# RGB_Panel_Shield_for_Arduino.net
KiCad netlist of a schematic drawn in EAGLE
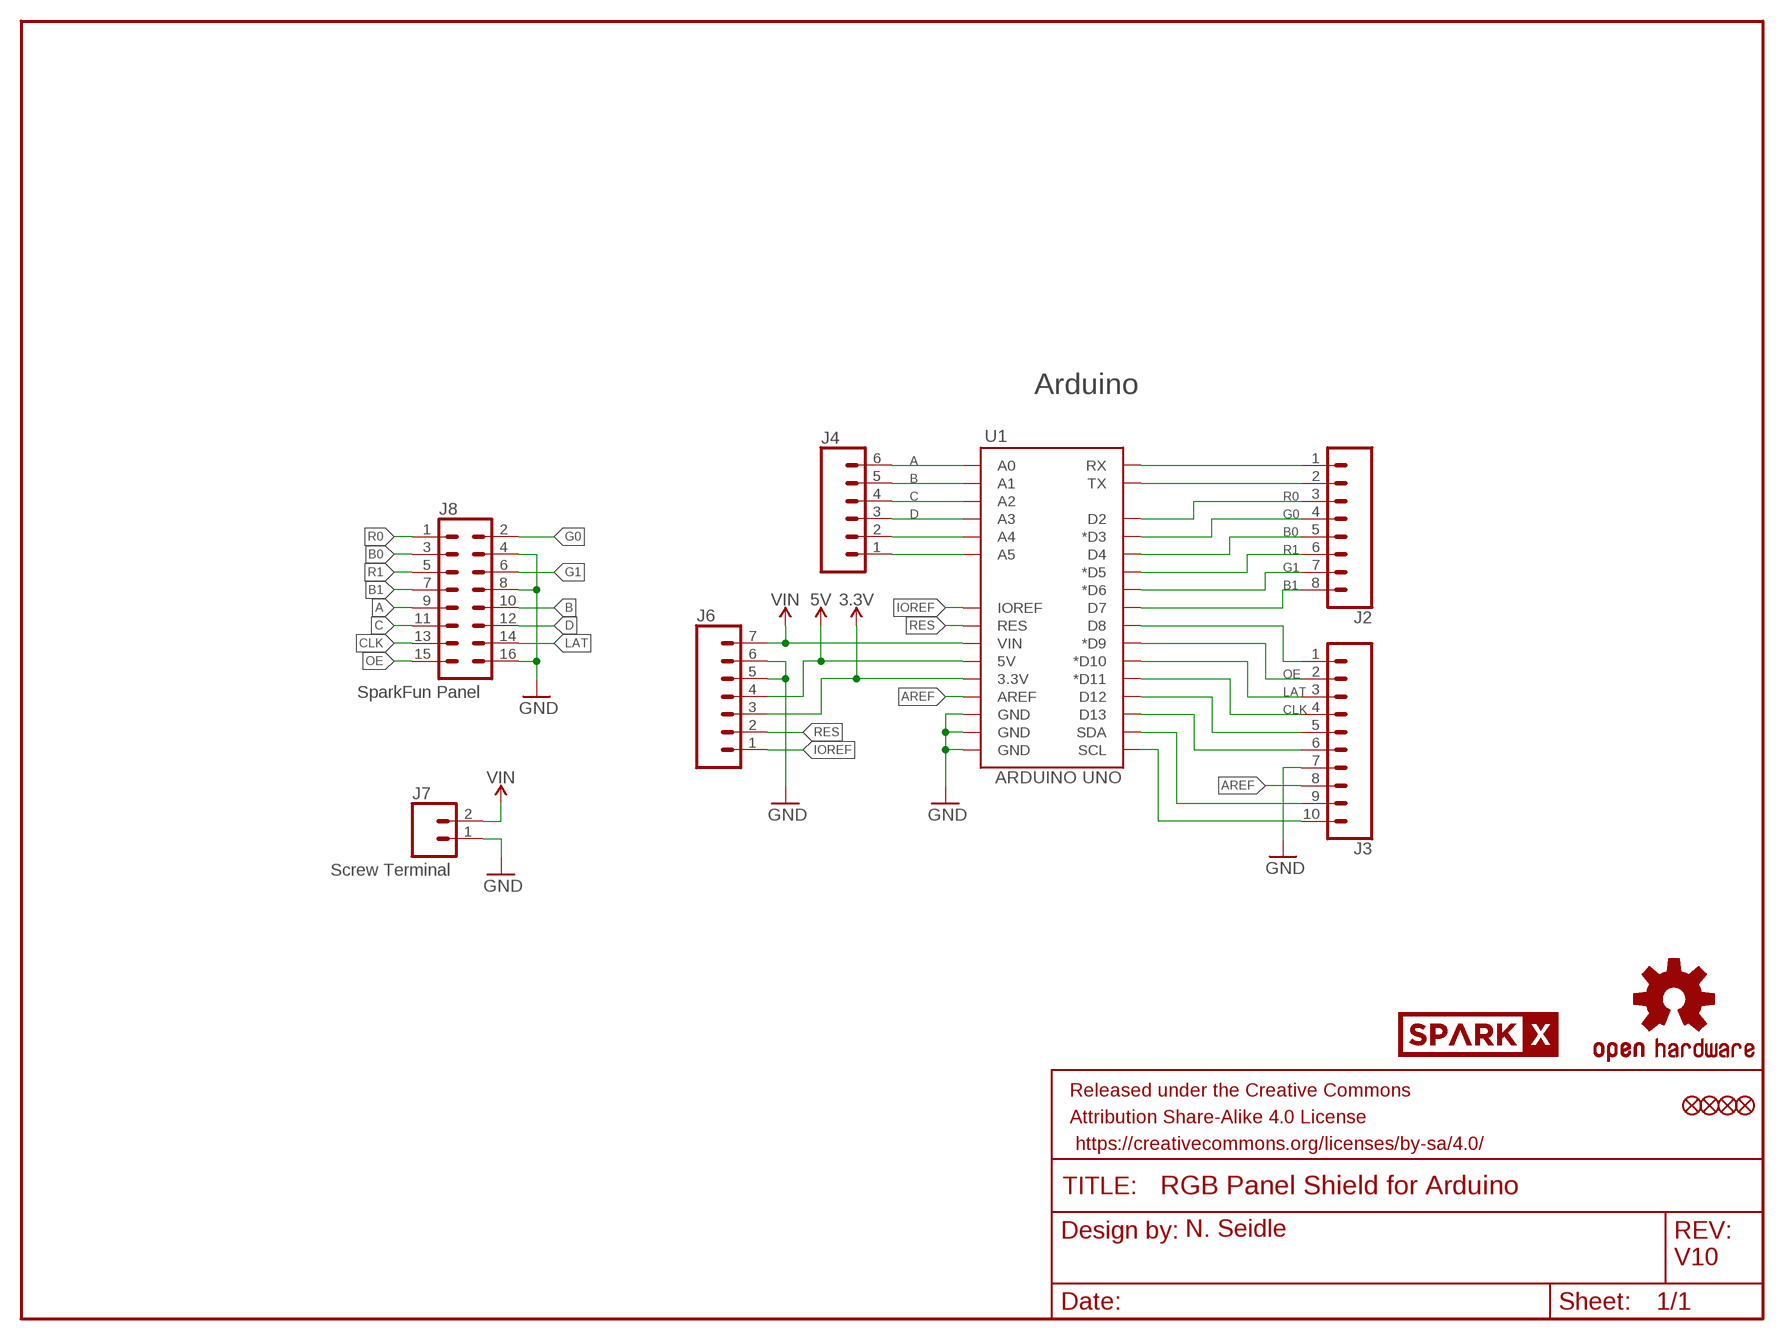
[diagram p0: schematic, sheet 1]

(export (version "E")
  (design (tool "Eeschema 10.0.6"))
  (components
    (comp (ref "FD1")
      (value "FIDUCIAL1X2")
      (footprint "eagle-import:FIDUCIAL-1X2")
      (libsource (lib "eagle-import") (part "FIDUCIAL1X2"))
    )
    (comp (ref "FD2")
      (value "FIDUCIAL1X2")
      (footprint "eagle-import:FIDUCIAL-1X2")
      (libsource (lib "eagle-import") (part "FIDUCIAL1X2"))
    )
    (comp (ref "FD3")
      (value "FIDUCIAL1X2")
      (footprint "eagle-import:FIDUCIAL-1X2")
      (libsource (lib "eagle-import") (part "FIDUCIAL1X2"))
    )
    (comp (ref "FD4")
      (value "FIDUCIAL1X2")
      (footprint "eagle-import:FIDUCIAL-1X2")
      (libsource (lib "eagle-import") (part "FIDUCIAL1X2"))
    )
    (comp (ref "FRAME1")
      (value "FRAME-LETTER")
      (footprint "eagle-import:CREATIVE_COMMONS")
      (libsource (lib "eagle-import") (part "FRAME-LETTER"))
    )
    (comp (ref "J2")
      (value "CONN_08NO_SILK_FEMALE_PTH")
      (footprint "eagle-import:1X08_NO_SILK")
      (libsource (lib "eagle-import") (part "CONN_08NO_SILK_FEMALE_PTH"))
    )
    (comp (ref "J3")
      (value "CONN_10NO_SILK_PTH_FEMALE")
      (footprint "eagle-import:1X10_NO_SILK")
      (libsource (lib "eagle-import") (part "CONN_10NO_SILK_PTH_FEMALE"))
    )
    (comp (ref "J4")
      (value "CONN_06NO_SILK_FEMALE_PTH")
      (footprint "eagle-import:1X06_NO_SILK")
      (libsource (lib "eagle-import") (part "CONN_06NO_SILK_FEMALE_PTH"))
    )
    (comp (ref "J6")
      (value "CONN_07NO_SILK")
      (footprint "eagle-import:1X07_NO_SILK")
      (libsource (lib "eagle-import") (part "CONN_07NO_SILK"))
    )
    (comp (ref "J7")
      (value "Screw Terminal")
      (footprint "eagle-import:SCREWTERMINAL-5MM-2")
      (libsource (lib "eagle-import") (part "CONN_025MM"))
    )
    (comp (ref "J8")
      (value "SparkFun Panel")
      (footprint "eagle-import:2X8-SHROUDED_LOCK")
      (libsource (lib "eagle-import") (part "CONN_08X2_SHROUD"))
    )
    (comp (ref "LOGO1")
      (value "OSHW-LOGOMINI")
      (footprint "eagle-import:OSHW-LOGO-MINI")
      (libsource (lib "eagle-import") (part "OSHW-LOGOMINI"))
    )
    (comp (ref "U$91")
      (value "SPARKX-LOGO4")
      (footprint "eagle-import:SPARKX-MEDIUM")
      (libsource (lib "eagle-import") (part "SPARKX-LOGO4"))
    )
    (comp (ref "U1")
      (value "ARDUINO UNO")
      (footprint "eagle-import:UNO_R3_SHIELD_NOLABELS")
      (libsource (lib "eagle-import") (part "ARDUINO_R3_SHIELDNOLABELS"))
    )
  )
  (nets
    (net (code "1") (name "3.3V") (class "Default")
      (node (ref "J6") (pin "3") (pinfunction "3_3") (pintype "passive"))
      (node (ref "U1") (pin "3.3V") (pinfunction "3.3V_3.3V") (pintype "bidirectional"))
    )
    (net (code "2") (name "5V") (class "Default")
      (node (ref "J6") (pin "4") (pinfunction "4_4") (pintype "passive"))
      (node (ref "U1") (pin "5V") (pinfunction "5V_5V") (pintype "bidirectional"))
    )
    (net (code "3") (name "A") (class "Default")
      (node (ref "J4") (pin "6") (pinfunction "6_6") (pintype "passive"))
      (node (ref "J8") (pin "9") (pinfunction "9_9") (pintype "passive"))
      (node (ref "U1") (pin "A0") (pinfunction "A0_A0") (pintype "bidirectional"))
    )
    (net (code "4") (name "AREF") (class "Default")
      (node (ref "J3") (pin "8") (pinfunction "8_8") (pintype "passive"))
      (node (ref "U1") (pin "AREF") (pinfunction "AREF_AREF") (pintype "bidirectional"))
    )
    (net (code "5") (name "B") (class "Default")
      (node (ref "J4") (pin "5") (pinfunction "5_5") (pintype "passive"))
      (node (ref "J8") (pin "10") (pinfunction "10_10") (pintype "passive"))
      (node (ref "U1") (pin "A1") (pinfunction "A1_A1") (pintype "bidirectional"))
    )
    (net (code "6") (name "B0") (class "Default")
      (node (ref "J2") (pin "5") (pinfunction "5_5") (pintype "passive"))
      (node (ref "J8") (pin "3") (pinfunction "3_3") (pintype "passive"))
      (node (ref "U1") (pin "D4") (pinfunction "D4_D4") (pintype "bidirectional"))
    )
    (net (code "7") (name "B1") (class "Default")
      (node (ref "J2") (pin "8") (pinfunction "8_8") (pintype "passive"))
      (node (ref "J8") (pin "7") (pinfunction "7_7") (pintype "passive"))
      (node (ref "U1") (pin "D7") (pinfunction "D7_D7") (pintype "bidirectional"))
    )
    (net (code "8") (name "C") (class "Default")
      (node (ref "J4") (pin "4") (pinfunction "4_4") (pintype "passive"))
      (node (ref "J8") (pin "11") (pinfunction "11_11") (pintype "passive"))
      (node (ref "U1") (pin "A2") (pinfunction "A2_A2") (pintype "bidirectional"))
    )
    (net (code "9") (name "CLK") (class "Default")
      (node (ref "J3") (pin "4") (pinfunction "4_4") (pintype "passive"))
      (node (ref "J8") (pin "13") (pinfunction "13_13") (pintype "passive"))
      (node (ref "U1") (pin "D11") (pinfunction "*D11_D11") (pintype "bidirectional"))
    )
    (net (code "10") (name "D") (class "Default")
      (node (ref "J4") (pin "3") (pinfunction "3_3") (pintype "passive"))
      (node (ref "J8") (pin "12") (pinfunction "12_12") (pintype "passive"))
      (node (ref "U1") (pin "A3") (pinfunction "A3_A3") (pintype "bidirectional"))
    )
    (net (code "11") (name "G0") (class "Default")
      (node (ref "J2") (pin "4") (pinfunction "4_4") (pintype "passive"))
      (node (ref "J8") (pin "2") (pinfunction "2_2") (pintype "passive"))
      (node (ref "U1") (pin "D3") (pinfunction "*D3_D3") (pintype "bidirectional"))
    )
    (net (code "12") (name "G1") (class "Default")
      (node (ref "J2") (pin "7") (pinfunction "7_7") (pintype "passive"))
      (node (ref "J8") (pin "6") (pinfunction "6_6") (pintype "passive"))
      (node (ref "U1") (pin "D6") (pinfunction "*D6_D6") (pintype "bidirectional"))
    )
    (net (code "13") (name "GND") (class "Default")
      (node (ref "J3") (pin "7") (pinfunction "7_7") (pintype "passive"))
      (node (ref "J6") (pin "5") (pinfunction "5_5") (pintype "passive"))
      (node (ref "J6") (pin "6") (pinfunction "6_6") (pintype "passive"))
      (node (ref "J7") (pin "1") (pinfunction "1_1") (pintype "passive"))
      (node (ref "J8") (pin "16") (pinfunction "16_16") (pintype "passive"))
      (node (ref "J8") (pin "4") (pinfunction "4_4") (pintype "passive"))
      (node (ref "J8") (pin "8") (pinfunction "8_8") (pintype "passive"))
      (node (ref "U1") (pin "GND@0") (pinfunction "GND_GND@0") (pintype "bidirectional"))
      (node (ref "U1") (pin "GND@1") (pinfunction "GND_GND@1") (pintype "bidirectional"))
      (node (ref "U1") (pin "GND@2") (pinfunction "GND_GND@2") (pintype "bidirectional"))
    )
    (net (code "14") (name "IOREF") (class "Default")
      (node (ref "J6") (pin "1") (pinfunction "1_1") (pintype "passive"))
      (node (ref "U1") (pin "IOREF") (pinfunction "IOREF_IOREF") (pintype "bidirectional"))
    )
    (net (code "15") (name "LAT") (class "Default")
      (node (ref "J3") (pin "3") (pinfunction "3_3") (pintype "passive"))
      (node (ref "J8") (pin "14") (pinfunction "14_14") (pintype "passive"))
      (node (ref "U1") (pin "D10") (pinfunction "*D10_D10") (pintype "bidirectional"))
    )
    (net (code "16") (name "Net-(J2-Pad1)") (class "Default")
      (node (ref "J2") (pin "1") (pinfunction "1_1") (pintype "passive"))
      (node (ref "U1") (pin "RX") (pinfunction "RX_RX") (pintype "bidirectional"))
    )
    (net (code "17") (name "Net-(J2-Pad2)") (class "Default")
      (node (ref "J2") (pin "2") (pinfunction "2_2") (pintype "passive"))
      (node (ref "U1") (pin "TX") (pinfunction "TX_TX") (pintype "bidirectional"))
    )
    (net (code "18") (name "Net-(J3-Pad1)") (class "Default")
      (node (ref "J3") (pin "1") (pinfunction "1_1") (pintype "passive"))
      (node (ref "U1") (pin "D8") (pinfunction "D8_D8") (pintype "bidirectional"))
    )
    (net (code "19") (name "Net-(J3-Pad5)") (class "Default")
      (node (ref "J3") (pin "5") (pinfunction "5_5") (pintype "passive"))
      (node (ref "U1") (pin "D12") (pinfunction "D12_D12") (pintype "bidirectional"))
    )
    (net (code "20") (name "Net-(J3-Pad6)") (class "Default")
      (node (ref "J3") (pin "6") (pinfunction "6_6") (pintype "passive"))
      (node (ref "U1") (pin "D13") (pinfunction "D13_D13") (pintype "bidirectional"))
    )
    (net (code "21") (name "Net-(J3-Pad9)") (class "Default")
      (node (ref "J3") (pin "9") (pinfunction "9_9") (pintype "passive"))
      (node (ref "U1") (pin "SDA") (pinfunction "SDA_SDA") (pintype "bidirectional"))
    )
    (net (code "22") (name "Net-(J3-Pad10)") (class "Default")
      (node (ref "J3") (pin "10") (pinfunction "10_10") (pintype "passive"))
      (node (ref "U1") (pin "SCL") (pinfunction "SCL_SCL") (pintype "bidirectional"))
    )
    (net (code "23") (name "Net-(J4-Pad1)") (class "Default")
      (node (ref "J4") (pin "1") (pinfunction "1_1") (pintype "passive"))
      (node (ref "U1") (pin "A5") (pinfunction "A5_A5") (pintype "bidirectional"))
    )
    (net (code "24") (name "Net-(J4-Pad2)") (class "Default")
      (node (ref "J4") (pin "2") (pinfunction "2_2") (pintype "passive"))
      (node (ref "U1") (pin "A4") (pinfunction "A4_A4") (pintype "bidirectional"))
    )
    (net (code "25") (name "OE") (class "Default")
      (node (ref "J3") (pin "2") (pinfunction "2_2") (pintype "passive"))
      (node (ref "J8") (pin "15") (pinfunction "15_15") (pintype "passive"))
      (node (ref "U1") (pin "D9") (pinfunction "*D9_D9") (pintype "bidirectional"))
    )
    (net (code "26") (name "R0") (class "Default")
      (node (ref "J2") (pin "3") (pinfunction "3_3") (pintype "passive"))
      (node (ref "J8") (pin "1") (pinfunction "1_1") (pintype "passive"))
      (node (ref "U1") (pin "D2") (pinfunction "D2_D2") (pintype "bidirectional"))
    )
    (net (code "27") (name "R1") (class "Default")
      (node (ref "J2") (pin "6") (pinfunction "6_6") (pintype "passive"))
      (node (ref "J8") (pin "5") (pinfunction "5_5") (pintype "passive"))
      (node (ref "U1") (pin "D5") (pinfunction "*D5_D5") (pintype "bidirectional"))
    )
    (net (code "28") (name "RES") (class "Default")
      (node (ref "J6") (pin "2") (pinfunction "2_2") (pintype "passive"))
      (node (ref "U1") (pin "RES") (pinfunction "RES_RES") (pintype "bidirectional"))
    )
    (net (code "29") (name "VIN") (class "Default")
      (node (ref "J6") (pin "7") (pinfunction "7_7") (pintype "passive"))
      (node (ref "J7") (pin "2") (pinfunction "2_2") (pintype "passive"))
      (node (ref "U1") (pin "VIN") (pinfunction "VIN_VIN") (pintype "bidirectional"))
    )
  )
)
